# max7219-martix.net
KiCad netlist of a schematic drawn in EAGLE
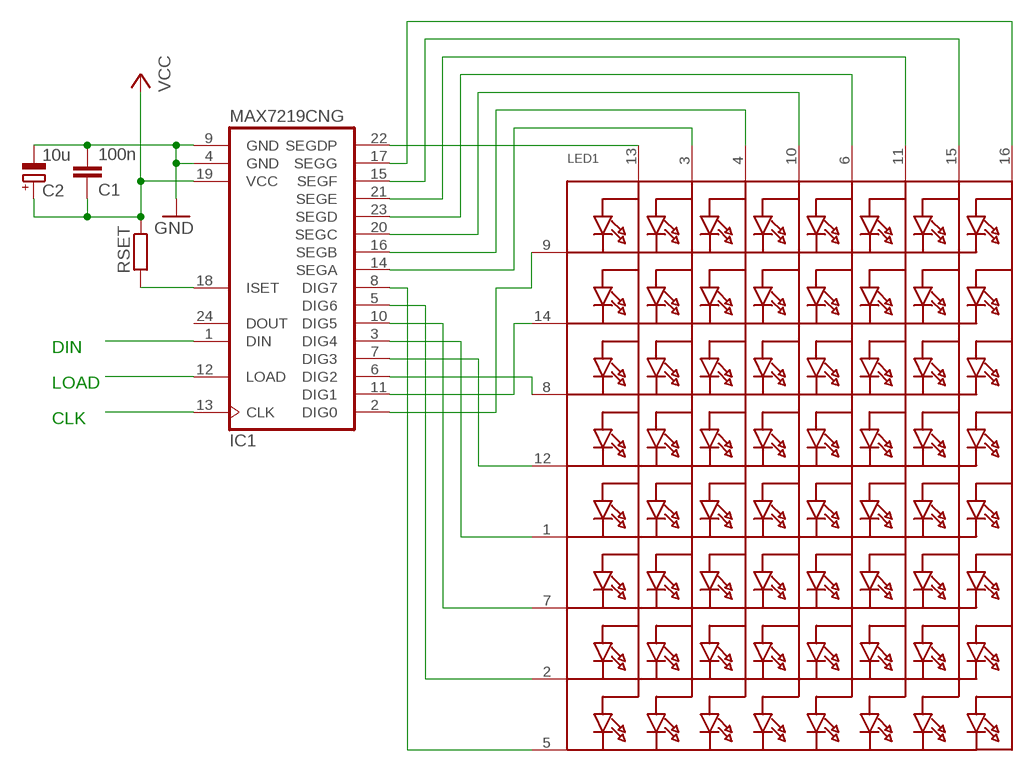
[diagram p0: schematic, sheet 1]

(export (version "E")
  (design (tool "Eeschema 10.0.6"))
  (components
    (comp (ref "C1")
      (value "100n")
      (footprint "eagle-import:C025-024X044")
      (libsource (lib "eagle-import") (part "C-EU025-024X044"))
    )
    (comp (ref "C2")
      (value "10u")
      (footprint "eagle-import:139CLL-2R")
      (libsource (lib "eagle-import") (part "CPOL-EU139CLL-2R"))
    )
    (comp (ref "IC1")
      (value "MAX7219CNG")
      (footprint "eagle-import:DIL24-3")
      (fields (field (name "MF") "MAXIM"))
      (libsource (lib "eagle-import") (part "MAX7219CNG"))
    )
    (comp (ref "LED1")
      (value "SEGMENT_8X8_ROWCATHODEM12A881UR")
      (footprint "eagle-import:SEGMENT_BL-M12A881UR")
      (libsource (lib "eagle-import") (part "SEGMENT_8X8_ROWCATHODEM12A881UR"))
    )
    (comp (ref "RSET")
      (value "R-EU_0204/7")
      (footprint "eagle-import:0204_7")
      (libsource (lib "eagle-import") (part "R-EU_0204/7"))
    )
  )
  (nets
    (net (code "1") (name "GND") (class "Default")
      (node (ref "C1") (pin "2") (pinfunction "2_2") (pintype "passive"))
      (node (ref "C2") (pin "-") (pinfunction "-_-") (pintype "passive"))
      (node (ref "IC1") (pin "4") (pinfunction "GND_4") (pintype "power_in"))
      (node (ref "IC1") (pin "9") (pinfunction "GND_9") (pintype "power_in"))
    )
    (net (code "2") (name "Net-(IC1-DIG0)") (class "Default")
      (node (ref "IC1") (pin "2") (pinfunction "DIG0_2") (pintype "output"))
      (node (ref "LED1") (pin "9") (pinfunction "K1_9") (pintype "bidirectional"))
    )
    (net (code "3") (name "Net-(IC1-DIG1)") (class "Default")
      (node (ref "IC1") (pin "11") (pinfunction "DIG1_11") (pintype "output"))
      (node (ref "LED1") (pin "14") (pinfunction "K2_14") (pintype "bidirectional"))
    )
    (net (code "4") (name "Net-(IC1-DIG2)") (class "Default")
      (node (ref "IC1") (pin "6") (pinfunction "DIG2_6") (pintype "output"))
      (node (ref "LED1") (pin "8") (pinfunction "K3_8") (pintype "bidirectional"))
    )
    (net (code "5") (name "Net-(IC1-DIG3)") (class "Default")
      (node (ref "IC1") (pin "7") (pinfunction "DIG3_7") (pintype "output"))
      (node (ref "LED1") (pin "12") (pinfunction "K4_12") (pintype "bidirectional"))
    )
    (net (code "6") (name "Net-(IC1-DIG4)") (class "Default")
      (node (ref "IC1") (pin "3") (pinfunction "DIG4_3") (pintype "output"))
      (node (ref "LED1") (pin "1") (pinfunction "K5_1") (pintype "bidirectional"))
    )
    (net (code "7") (name "Net-(IC1-DIG5)") (class "Default")
      (node (ref "IC1") (pin "10") (pinfunction "DIG5_10") (pintype "output"))
      (node (ref "LED1") (pin "7") (pinfunction "K6_7") (pintype "bidirectional"))
    )
    (net (code "8") (name "Net-(IC1-DIG6)") (class "Default")
      (node (ref "IC1") (pin "5") (pinfunction "DIG6_5") (pintype "output"))
      (node (ref "LED1") (pin "2") (pinfunction "K7_2") (pintype "bidirectional"))
    )
    (net (code "9") (name "Net-(IC1-DIG7)") (class "Default")
      (node (ref "IC1") (pin "8") (pinfunction "DIG7_8") (pintype "output"))
      (node (ref "LED1") (pin "5") (pinfunction "K8_5") (pintype "bidirectional"))
    )
    (net (code "10") (name "Net-(IC1-ISET)") (class "Default")
      (node (ref "IC1") (pin "18") (pinfunction "ISET_18") (pintype "input"))
      (node (ref "RSET") (pin "2") (pinfunction "2_2") (pintype "passive"))
    )
    (net (code "11") (name "Net-(IC1-SEGA)") (class "Default")
      (node (ref "IC1") (pin "14") (pinfunction "SEGA_14") (pintype "output"))
      (node (ref "LED1") (pin "3") (pinfunction "A2_3") (pintype "bidirectional"))
    )
    (net (code "12") (name "Net-(IC1-SEGB)") (class "Default")
      (node (ref "IC1") (pin "16") (pinfunction "SEGB_16") (pintype "output"))
      (node (ref "LED1") (pin "4") (pinfunction "A3_4") (pintype "bidirectional"))
    )
    (net (code "13") (name "Net-(IC1-SEGC)") (class "Default")
      (node (ref "IC1") (pin "20") (pinfunction "SEGC_20") (pintype "output"))
      (node (ref "LED1") (pin "10") (pinfunction "A4_10") (pintype "bidirectional"))
    )
    (net (code "14") (name "Net-(IC1-SEGD)") (class "Default")
      (node (ref "IC1") (pin "23") (pinfunction "SEGD_23") (pintype "output"))
      (node (ref "LED1") (pin "6") (pinfunction "A5_6") (pintype "bidirectional"))
    )
    (net (code "15") (name "Net-(IC1-SEGDP)") (class "Default")
      (node (ref "IC1") (pin "22") (pinfunction "SEGDP_22") (pintype "output"))
      (node (ref "LED1") (pin "13") (pinfunction "A1_13") (pintype "bidirectional"))
    )
    (net (code "16") (name "Net-(IC1-SEGE)") (class "Default")
      (node (ref "IC1") (pin "21") (pinfunction "SEGE_21") (pintype "output"))
      (node (ref "LED1") (pin "11") (pinfunction "A6_11") (pintype "bidirectional"))
    )
    (net (code "17") (name "Net-(IC1-SEGF)") (class "Default")
      (node (ref "IC1") (pin "15") (pinfunction "SEGF_15") (pintype "output"))
      (node (ref "LED1") (pin "15") (pinfunction "A7_15") (pintype "bidirectional"))
    )
    (net (code "18") (name "Net-(IC1-SEGG)") (class "Default")
      (node (ref "IC1") (pin "17") (pinfunction "SEGG_17") (pintype "output"))
      (node (ref "LED1") (pin "16") (pinfunction "A8_16") (pintype "bidirectional"))
    )
    (net (code "19") (name "VCC") (class "Default")
      (node (ref "C1") (pin "1") (pinfunction "1_1") (pintype "passive"))
      (node (ref "C2") (pin "+") (pinfunction "+_+") (pintype "passive"))
      (node (ref "IC1") (pin "19") (pinfunction "VCC_19") (pintype "power_in"))
      (node (ref "RSET") (pin "1") (pinfunction "1_1") (pintype "passive"))
    )
    (net (code "20") (name "unconnected-(IC1-CLK-Pad13)") (class "Default")
      (node (ref "IC1") (pin "13") (pinfunction "CLK_13") (pintype "input"))
    )
    (net (code "21") (name "unconnected-(IC1-DIN-Pad1)") (class "Default")
      (node (ref "IC1") (pin "1") (pinfunction "DIN_1") (pintype "input"))
    )
    (net (code "22") (name "unconnected-(IC1-DOUT-Pad24)") (class "Default")
      (node (ref "IC1") (pin "24") (pinfunction "DOUT_24") (pintype "output"))
    )
    (net (code "23") (name "unconnected-(IC1-LOAD-Pad12)") (class "Default")
      (node (ref "IC1") (pin "12") (pinfunction "LOAD_12") (pintype "input"))
    )
  )
)
